# Robotics_Booster_Pack.net
KiCad netlist of a schematic drawn in EAGLE
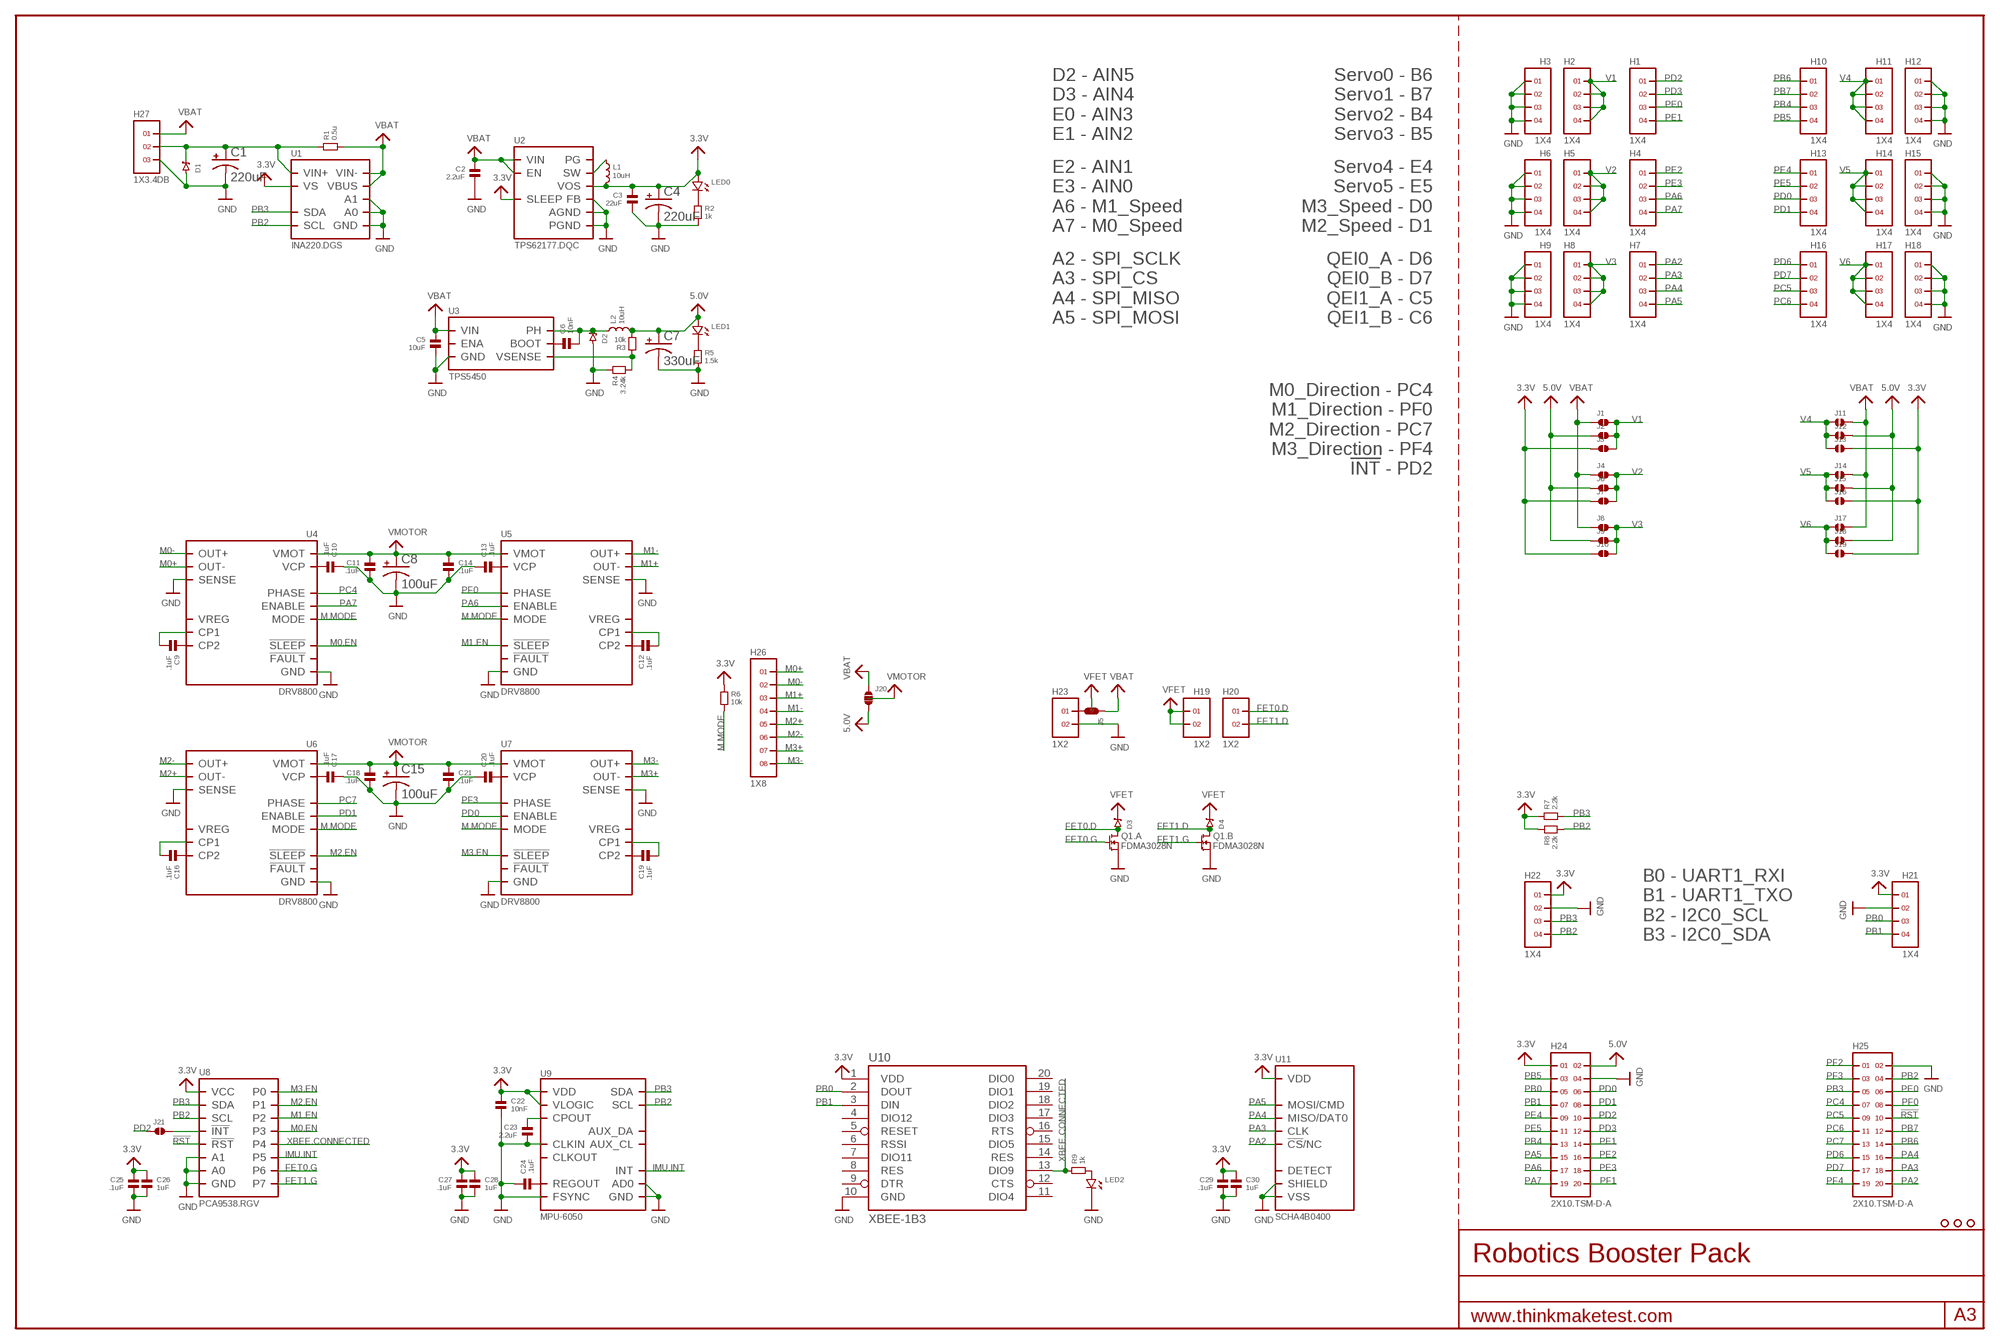
[diagram p0: schematic, sheet 1]

(export (version "E")
  (design (tool "Eeschema 10.0.6"))
  (components
    (comp (ref "C1")
      (value "220uF")
      (footprint "eagle-import:PANASONIC_E")
      (libsource (lib "eagle-import") (part "CPOL-USE"))
    )
    (comp (ref "C2")
      (value "2.2uF")
      (footprint "eagle-import:0603")
      (libsource (lib "eagle-import") (part "CAPACITOR.0603"))
    )
    (comp (ref "C3")
      (value "22uF")
      (footprint "eagle-import:0805")
      (libsource (lib "eagle-import") (part "CAPACITOR.0805"))
    )
    (comp (ref "C4")
      (value "220uF")
      (footprint "eagle-import:PANASONIC_E")
      (libsource (lib "eagle-import") (part "CPOL-USE"))
    )
    (comp (ref "C5")
      (value "10uF")
      (footprint "eagle-import:1206")
      (libsource (lib "eagle-import") (part "CAPACITOR.1206"))
    )
    (comp (ref "C6")
      (value "10nF")
      (footprint "eagle-import:0603")
      (libsource (lib "eagle-import") (part "CAPACITOR.0603"))
    )
    (comp (ref "C7")
      (value "330uF")
      (footprint "eagle-import:PANASONIC_E")
      (libsource (lib "eagle-import") (part "CPOL-USE"))
    )
    (comp (ref "C8")
      (value "100uF")
      (footprint "eagle-import:PANASONIC_E")
      (libsource (lib "eagle-import") (part "CPOL-USE"))
    )
    (comp (ref "C9")
      (value ".1uF")
      (footprint "eagle-import:0603")
      (libsource (lib "eagle-import") (part "CAPACITOR.0603"))
    )
    (comp (ref "C10")
      (value ".1uF")
      (footprint "eagle-import:0603")
      (libsource (lib "eagle-import") (part "CAPACITOR.0603"))
    )
    (comp (ref "C11")
      (value ".1uF")
      (footprint "eagle-import:0603")
      (libsource (lib "eagle-import") (part "CAPACITOR.0603"))
    )
    (comp (ref "C12")
      (value ".1uF")
      (footprint "eagle-import:0603")
      (libsource (lib "eagle-import") (part "CAPACITOR.0603"))
    )
    (comp (ref "C13")
      (value ".1uF")
      (footprint "eagle-import:0603")
      (libsource (lib "eagle-import") (part "CAPACITOR.0603"))
    )
    (comp (ref "C14")
      (value ".1uF")
      (footprint "eagle-import:0603")
      (libsource (lib "eagle-import") (part "CAPACITOR.0603"))
    )
    (comp (ref "C15")
      (value "100uF")
      (footprint "eagle-import:PANASONIC_E")
      (libsource (lib "eagle-import") (part "CPOL-USE"))
    )
    (comp (ref "C16")
      (value ".1uF")
      (footprint "eagle-import:0603")
      (libsource (lib "eagle-import") (part "CAPACITOR.0603"))
    )
    (comp (ref "C17")
      (value ".1uF")
      (footprint "eagle-import:0603")
      (libsource (lib "eagle-import") (part "CAPACITOR.0603"))
    )
    (comp (ref "C18")
      (value ".1uF")
      (footprint "eagle-import:0603")
      (libsource (lib "eagle-import") (part "CAPACITOR.0603"))
    )
    (comp (ref "C19")
      (value ".1uF")
      (footprint "eagle-import:0603")
      (libsource (lib "eagle-import") (part "CAPACITOR.0603"))
    )
    (comp (ref "C20")
      (value ".1uF")
      (footprint "eagle-import:0603")
      (libsource (lib "eagle-import") (part "CAPACITOR.0603"))
    )
    (comp (ref "C21")
      (value ".1uF")
      (footprint "eagle-import:0603")
      (libsource (lib "eagle-import") (part "CAPACITOR.0603"))
    )
    (comp (ref "C22")
      (value "10nF")
      (footprint "eagle-import:0603")
      (libsource (lib "eagle-import") (part "CAPACITOR.0603"))
    )
    (comp (ref "C23")
      (value "2.2uF")
      (footprint "eagle-import:0603")
      (libsource (lib "eagle-import") (part "CAPACITOR.0603"))
    )
    (comp (ref "C24")
      (value ".1uF")
      (footprint "eagle-import:0603")
      (libsource (lib "eagle-import") (part "CAPACITOR.0603"))
    )
    (comp (ref "C25")
      (value ".1uF")
      (footprint "eagle-import:0603")
      (libsource (lib "eagle-import") (part "CAPACITOR.0603"))
    )
    (comp (ref "C26")
      (value "1uF")
      (footprint "eagle-import:0603")
      (libsource (lib "eagle-import") (part "CAPACITOR.0603"))
    )
    (comp (ref "C27")
      (value ".1uF")
      (footprint "eagle-import:0603")
      (libsource (lib "eagle-import") (part "CAPACITOR.0603"))
    )
    (comp (ref "C28")
      (value "1uF")
      (footprint "eagle-import:0603")
      (libsource (lib "eagle-import") (part "CAPACITOR.0603"))
    )
    (comp (ref "C29")
      (value ".1uF")
      (footprint "eagle-import:0603")
      (libsource (lib "eagle-import") (part "CAPACITOR.0603"))
    )
    (comp (ref "C30")
      (value "1uF")
      (footprint "eagle-import:0603")
      (libsource (lib "eagle-import") (part "CAPACITOR.0603"))
    )
    (comp (ref "D1")
      (value "CDBMT2100-HF")
      (footprint "eagle-import:SOD-123H")
      (libsource (lib "eagle-import") (part "CDBMT____-HF"))
    )
    (comp (ref "D2")
      (value "CDBC5XXX-G")
      (footprint "eagle-import:DO-214AB")
      (libsource (lib "eagle-import") (part "CDBC5XXX-G"))
    )
    (comp (ref "D3")
      (value "CDBMT2100-HF")
      (footprint "eagle-import:SOD-123H")
      (libsource (lib "eagle-import") (part "CDBMT____-HF"))
    )
    (comp (ref "D4")
      (value "CDBMT2100-HF")
      (footprint "eagle-import:SOD-123H")
      (libsource (lib "eagle-import") (part "CDBMT____-HF"))
    )
    (comp (ref "H1")
      (value "1X4")
      (footprint "eagle-import:1X4")
      (libsource (lib "eagle-import") (part "1X4"))
    )
    (comp (ref "H2")
      (value "1X4")
      (footprint "eagle-import:1X4")
      (libsource (lib "eagle-import") (part "1X4"))
    )
    (comp (ref "H3")
      (value "1X4")
      (footprint "eagle-import:1X4")
      (libsource (lib "eagle-import") (part "1X4"))
    )
    (comp (ref "H4")
      (value "1X4")
      (footprint "eagle-import:1X4")
      (libsource (lib "eagle-import") (part "1X4"))
    )
    (comp (ref "H5")
      (value "1X4")
      (footprint "eagle-import:1X4")
      (libsource (lib "eagle-import") (part "1X4"))
    )
    (comp (ref "H6")
      (value "1X4")
      (footprint "eagle-import:1X4")
      (libsource (lib "eagle-import") (part "1X4"))
    )
    (comp (ref "H7")
      (value "1X4")
      (footprint "eagle-import:1X4")
      (libsource (lib "eagle-import") (part "1X4"))
    )
    (comp (ref "H8")
      (value "1X4")
      (footprint "eagle-import:1X4")
      (libsource (lib "eagle-import") (part "1X4"))
    )
    (comp (ref "H9")
      (value "1X4")
      (footprint "eagle-import:1X4")
      (libsource (lib "eagle-import") (part "1X4"))
    )
    (comp (ref "H10")
      (value "1X4")
      (footprint "eagle-import:1X4")
      (libsource (lib "eagle-import") (part "1X4"))
    )
    (comp (ref "H11")
      (value "1X4")
      (footprint "eagle-import:1X4")
      (libsource (lib "eagle-import") (part "1X4"))
    )
    (comp (ref "H12")
      (value "1X4")
      (footprint "eagle-import:1X4")
      (libsource (lib "eagle-import") (part "1X4"))
    )
    (comp (ref "H13")
      (value "1X4")
      (footprint "eagle-import:1X4")
      (libsource (lib "eagle-import") (part "1X4"))
    )
    (comp (ref "H14")
      (value "1X4")
      (footprint "eagle-import:1X4")
      (libsource (lib "eagle-import") (part "1X4"))
    )
    (comp (ref "H15")
      (value "1X4")
      (footprint "eagle-import:1X4")
      (libsource (lib "eagle-import") (part "1X4"))
    )
    (comp (ref "H16")
      (value "1X4")
      (footprint "eagle-import:1X4")
      (libsource (lib "eagle-import") (part "1X4"))
    )
    (comp (ref "H17")
      (value "1X4")
      (footprint "eagle-import:1X4")
      (libsource (lib "eagle-import") (part "1X4"))
    )
    (comp (ref "H18")
      (value "1X4")
      (footprint "eagle-import:1X4")
      (libsource (lib "eagle-import") (part "1X4"))
    )
    (comp (ref "H19")
      (value "1X2")
      (footprint "eagle-import:1X2")
      (libsource (lib "eagle-import") (part "1X2"))
    )
    (comp (ref "H20")
      (value "1X2")
      (footprint "eagle-import:1X2")
      (libsource (lib "eagle-import") (part "1X2"))
    )
    (comp (ref "H21")
      (value "1X4")
      (footprint "eagle-import:1X4")
      (libsource (lib "eagle-import") (part "1X4"))
    )
    (comp (ref "H22")
      (value "1X4")
      (footprint "eagle-import:1X4")
      (libsource (lib "eagle-import") (part "1X4"))
    )
    (comp (ref "H23")
      (value "1X2")
      (footprint "eagle-import:1X2")
      (libsource (lib "eagle-import") (part "1X2"))
    )
    (comp (ref "H24")
      (value "2X10.TSM-D-A")
      (footprint "eagle-import:TSM-110-XX-XXX-DV-A")
      (libsource (lib "eagle-import") (part "2X10.TSM-D-A"))
    )
    (comp (ref "H25")
      (value "2X10.TSM-D-A")
      (footprint "eagle-import:TSM-110-XX-XXX-DV-A")
      (libsource (lib "eagle-import") (part "2X10.TSM-D-A"))
    )
    (comp (ref "H26")
      (value "1X8")
      (footprint "eagle-import:1824480000")
      (libsource (lib "eagle-import") (part "1X8"))
    )
    (comp (ref "H27")
      (value "1X3.4DB")
      (footprint "eagle-import:4DB-P108-02")
      (libsource (lib "eagle-import") (part "1X3.4DB"))
    )
    (comp (ref "J1")
      (value "SOLDERJUMPER.2.LRG")
      (footprint "eagle-import:2.LRG")
      (libsource (lib "eagle-import") (part "SOLDERJUMPER.2.LRG"))
    )
    (comp (ref "J2")
      (value "SOLDERJUMPER.2.LRG")
      (footprint "eagle-import:2.LRG")
      (libsource (lib "eagle-import") (part "SOLDERJUMPER.2.LRG"))
    )
    (comp (ref "J3")
      (value "SOLDERJUMPER.2.LRG.PASTE")
      (footprint "eagle-import:2.LRG.PASTE")
      (libsource (lib "eagle-import") (part "SOLDERJUMPER.2.LRG.PASTE"))
    )
    (comp (ref "J4")
      (value "SOLDERJUMPER.2.LRG")
      (footprint "eagle-import:2.LRG")
      (libsource (lib "eagle-import") (part "SOLDERJUMPER.2.LRG"))
    )
    (comp (ref "J5")
      (value "SOLDERJUMPER.3.LRG.12")
      (footprint "eagle-import:3.LRG.12")
      (libsource (lib "eagle-import") (part "SOLDERJUMPER.3.LRG.12"))
    )
    (comp (ref "J6")
      (value "SOLDERJUMPER.2.LRG")
      (footprint "eagle-import:2.LRG")
      (libsource (lib "eagle-import") (part "SOLDERJUMPER.2.LRG"))
    )
    (comp (ref "J7")
      (value "SOLDERJUMPER.2.LRG.PASTE")
      (footprint "eagle-import:2.LRG.PASTE")
      (libsource (lib "eagle-import") (part "SOLDERJUMPER.2.LRG.PASTE"))
    )
    (comp (ref "J8")
      (value "SOLDERJUMPER.2.LRG")
      (footprint "eagle-import:2.LRG")
      (libsource (lib "eagle-import") (part "SOLDERJUMPER.2.LRG"))
    )
    (comp (ref "J9")
      (value "SOLDERJUMPER.2.LRG")
      (footprint "eagle-import:2.LRG")
      (libsource (lib "eagle-import") (part "SOLDERJUMPER.2.LRG"))
    )
    (comp (ref "J10")
      (value "SOLDERJUMPER.2.LRG.PASTE")
      (footprint "eagle-import:2.LRG.PASTE")
      (libsource (lib "eagle-import") (part "SOLDERJUMPER.2.LRG.PASTE"))
    )
    (comp (ref "J11")
      (value "SOLDERJUMPER.2.LRG")
      (footprint "eagle-import:2.LRG")
      (libsource (lib "eagle-import") (part "SOLDERJUMPER.2.LRG"))
    )
    (comp (ref "J12")
      (value "SOLDERJUMPER.2.LRG.PASTE")
      (footprint "eagle-import:2.LRG.PASTE")
      (libsource (lib "eagle-import") (part "SOLDERJUMPER.2.LRG.PASTE"))
    )
    (comp (ref "J13")
      (value "SOLDERJUMPER.2.LRG")
      (footprint "eagle-import:2.LRG")
      (libsource (lib "eagle-import") (part "SOLDERJUMPER.2.LRG"))
    )
    (comp (ref "J14")
      (value "SOLDERJUMPER.2.LRG")
      (footprint "eagle-import:2.LRG")
      (libsource (lib "eagle-import") (part "SOLDERJUMPER.2.LRG"))
    )
    (comp (ref "J15")
      (value "SOLDERJUMPER.2.LRG")
      (footprint "eagle-import:2.LRG")
      (libsource (lib "eagle-import") (part "SOLDERJUMPER.2.LRG"))
    )
    (comp (ref "J16")
      (value "SOLDERJUMPER.2.LRG.PASTE")
      (footprint "eagle-import:2.LRG.PASTE")
      (libsource (lib "eagle-import") (part "SOLDERJUMPER.2.LRG.PASTE"))
    )
    (comp (ref "J17")
      (value "SOLDERJUMPER.2.LRG")
      (footprint "eagle-import:2.LRG")
      (libsource (lib "eagle-import") (part "SOLDERJUMPER.2.LRG"))
    )
    (comp (ref "J18")
      (value "SOLDERJUMPER.2.LRG")
      (footprint "eagle-import:2.LRG")
      (libsource (lib "eagle-import") (part "SOLDERJUMPER.2.LRG"))
    )
    (comp (ref "J19")
      (value "SOLDERJUMPER.2.LRG.PASTE")
      (footprint "eagle-import:2.LRG.PASTE")
      (libsource (lib "eagle-import") (part "SOLDERJUMPER.2.LRG.PASTE"))
    )
    (comp (ref "J20")
      (value "SOLDERJUMPER.3.LRG.12")
      (footprint "eagle-import:3.LRG.12")
      (libsource (lib "eagle-import") (part "SOLDERJUMPER.3.LRG.12"))
    )
    (comp (ref "J21")
      (value "SOLDERJUMPER.2.LRG")
      (footprint "eagle-import:2.LRG")
      (libsource (lib "eagle-import") (part "SOLDERJUMPER.2.LRG"))
    )
    (comp (ref "L1")
      (value "10uH")
      (footprint "eagle-import:SRN6045")
      (libsource (lib "eagle-import") (part "INDUCTOR-SRN6045"))
    )
    (comp (ref "L2")
      (value "10uH")
      (footprint "eagle-import:XAL6060")
      (libsource (lib "eagle-import") (part "INDUCTOR.XAL6060"))
    )
    (comp (ref "LED0")
      (value "LED.0603")
      (footprint "eagle-import:0603.LED")
      (libsource (lib "eagle-import") (part "LED.0603"))
    )
    (comp (ref "LED1")
      (value "LED.0603")
      (footprint "eagle-import:0603.LED")
      (libsource (lib "eagle-import") (part "LED.0603"))
    )
    (comp (ref "LED2")
      (value "LED.0603")
      (footprint "eagle-import:0603.LED")
      (libsource (lib "eagle-import") (part "LED.0603"))
    )
    (comp (ref "Q1")
      (value "FDMA3028N")
      (footprint "eagle-import:MICROFET.2X2")
      (libsource (lib "eagle-import") (part "FDMA"))
    )
    (comp (ref "R1")
      (value "0.5u")
      (footprint "eagle-import:2512")
      (libsource (lib "eagle-import") (part "RESISTOR.2512"))
    )
    (comp (ref "R2")
      (value "1k")
      (footprint "eagle-import:0603")
      (libsource (lib "eagle-import") (part "RESISTOR.0603"))
    )
    (comp (ref "R3")
      (value "10k")
      (footprint "eagle-import:0603")
      (libsource (lib "eagle-import") (part "RESISTOR.0603"))
    )
    (comp (ref "R4")
      (value "3.24k")
      (footprint "eagle-import:0603")
      (libsource (lib "eagle-import") (part "RESISTOR.0603"))
    )
    (comp (ref "R5")
      (value "1.5k")
      (footprint "eagle-import:0603")
      (libsource (lib "eagle-import") (part "RESISTOR.0603"))
    )
    (comp (ref "R6")
      (value "10k")
      (footprint "eagle-import:0603")
      (libsource (lib "eagle-import") (part "RESISTOR.0603"))
    )
    (comp (ref "R7")
      (value "2.2k")
      (footprint "eagle-import:0603")
      (libsource (lib "eagle-import") (part "RESISTOR.0603"))
    )
    (comp (ref "R8")
      (value "2.2k")
      (footprint "eagle-import:0603")
      (libsource (lib "eagle-import") (part "RESISTOR.0603"))
    )
    (comp (ref "R9")
      (value "1k")
      (footprint "eagle-import:0603")
      (libsource (lib "eagle-import") (part "RESISTOR.0603"))
    )
    (comp (ref "U$3")
      (value "HOLE.4MM")
      (footprint "eagle-import:#4")
      (libsource (lib "eagle-import") (part "HOLE.4MM"))
    )
    (comp (ref "U$4")
      (value "HOLE.4MM")
      (footprint "eagle-import:#4")
      (libsource (lib "eagle-import") (part "HOLE.4MM"))
    )
    (comp (ref "U$21")
      (value "HOLE.4MM")
      (footprint "eagle-import:#4")
      (libsource (lib "eagle-import") (part "HOLE.4MM"))
    )
    (comp (ref "U1")
      (value "INA220.DGS")
      (footprint "eagle-import:DGS.10")
      (libsource (lib "eagle-import") (part "INA220.DGS"))
    )
    (comp (ref "U2")
      (value "TPS62177.DQC")
      (footprint "eagle-import:DQC")
      (libsource (lib "eagle-import") (part "TPS62177.DQC"))
    )
    (comp (ref "U3")
      (value "TPS5450")
      (footprint "eagle-import:DDA")
      (libsource (lib "eagle-import") (part "TPS54X0"))
    )
    (comp (ref "U4")
      (value "DRV8800")
      (footprint "eagle-import:RTY.16")
      (libsource (lib "eagle-import") (part "DRV8800.RTY"))
    )
    (comp (ref "U5")
      (value "DRV8800")
      (footprint "eagle-import:RTY.16")
      (libsource (lib "eagle-import") (part "DRV8800.RTY"))
    )
    (comp (ref "U6")
      (value "DRV8800")
      (footprint "eagle-import:RTY.16")
      (libsource (lib "eagle-import") (part "DRV8800.RTY"))
    )
    (comp (ref "U7")
      (value "DRV8800")
      (footprint "eagle-import:RTY.16")
      (libsource (lib "eagle-import") (part "DRV8800.RTY"))
    )
    (comp (ref "U8")
      (value "PCA9538.RGV")
      (footprint "eagle-import:RGV.16")
      (libsource (lib "eagle-import") (part "PCA9538.RGV"))
    )
    (comp (ref "U9")
      (value "MPU-6050")
      (footprint "eagle-import:QFN.24.4X4")
      (libsource (lib "eagle-import") (part "MPU-6050"))
    )
    (comp (ref "U10")
      (value "XBEE-1B3")
      (footprint "eagle-import:XBEE-SMD")
      (libsource (lib "eagle-import") (part "XBEE-1B3"))
    )
    (comp (ref "U11")
      (value "SCHA4B0400")
      (footprint "eagle-import:SCHA4B0400")
      (libsource (lib "eagle-import") (part "SCHA4B0400"))
    )
  )
  (nets
    (net (code "1") (name "/FET0.D") (class "Default")
      (node (ref "D3") (pin "2") (pinfunction "2_2") (pintype "bidirectional"))
      (node (ref "H20") (pin "1") (pinfunction "1_1") (pintype "bidirectional"))
      (node (ref "Q1") (pin "6") (pinfunction "D_6") (pintype "bidirectional"))
      (node (ref "Q1") (pin "PAD@1") (pinfunction "D_PAD@1") (pintype "bidirectional"))
    )
    (net (code "2") (name "/FET0.G") (class "Default")
      (node (ref "Q1") (pin "2") (pinfunction "G_2") (pintype "bidirectional"))
      (node (ref "U8") (pin "9") (pinfunction "P6_9") (pintype "bidirectional"))
    )
    (net (code "3") (name "/FET1.D") (class "Default")
      (node (ref "D4") (pin "2") (pinfunction "2_2") (pintype "bidirectional"))
      (node (ref "H20") (pin "2") (pinfunction "2_2") (pintype "bidirectional"))
      (node (ref "Q1") (pin "3") (pinfunction "D_3") (pintype "bidirectional"))
      (node (ref "Q1") (pin "PAD@2") (pinfunction "D_PAD@2") (pintype "bidirectional"))
    )
    (net (code "4") (name "/FET1.G") (class "Default")
      (node (ref "Q1") (pin "5") (pinfunction "G_5") (pintype "bidirectional"))
      (node (ref "U8") (pin "10") (pinfunction "P7_10") (pintype "bidirectional"))
    )
    (net (code "5") (name "/IMU.INT") (class "Default")
      (node (ref "U8") (pin "8") (pinfunction "P5_8") (pintype "bidirectional"))
      (node (ref "U9") (pin "12") (pinfunction "INT_12") (pintype "bidirectional"))
    )
    (net (code "6") (name "/M.MODE") (class "Default")
      (node (ref "R6") (pin "2") (pinfunction "2_2") (pintype "bidirectional"))
      (node (ref "U4") (pin "16") (pinfunction "MODE_16") (pintype "bidirectional"))
      (node (ref "U5") (pin "16") (pinfunction "MODE_16") (pintype "bidirectional"))
      (node (ref "U6") (pin "16") (pinfunction "MODE_16") (pintype "bidirectional"))
      (node (ref "U7") (pin "16") (pinfunction "MODE_16") (pintype "bidirectional"))
    )
    (net (code "7") (name "/M0+") (class "Default")
      (node (ref "H26") (pin "1@1") (pinfunction "1_1@1") (pintype "bidirectional"))
      (node (ref "H26") (pin "1@2") (pinfunction "1_1@2") (pintype "bidirectional"))
      (node (ref "U4") (pin "9") (pinfunction "OUT-_9") (pintype "bidirectional"))
    )
    (net (code "8") (name "/M0-") (class "Default")
      (node (ref "H26") (pin "2@1") (pinfunction "2_2@1") (pintype "bidirectional"))
      (node (ref "H26") (pin "2@2") (pinfunction "2_2@2") (pintype "bidirectional"))
      (node (ref "U4") (pin "6") (pinfunction "OUT+_6") (pintype "bidirectional"))
    )
    (net (code "9") (name "/M0.EN") (class "Default")
      (node (ref "U4") (pin "3") (pinfunction "~{SLEEP}_3") (pintype "bidirectional"))
      (node (ref "U8") (pin "5") (pinfunction "P3_5") (pintype "bidirectional"))
    )
    (net (code "10") (name "/M1+") (class "Default")
      (node (ref "H26") (pin "3@1") (pinfunction "3_3@1") (pintype "bidirectional"))
      (node (ref "H26") (pin "3@2") (pinfunction "3_3@2") (pintype "bidirectional"))
      (node (ref "U5") (pin "9") (pinfunction "OUT-_9") (pintype "bidirectional"))
    )
    (net (code "11") (name "/M1-") (class "Default")
      (node (ref "H26") (pin "4@1") (pinfunction "4_4@1") (pintype "bidirectional"))
      (node (ref "H26") (pin "4@2") (pinfunction "4_4@2") (pintype "bidirectional"))
      (node (ref "U5") (pin "6") (pinfunction "OUT+_6") (pintype "bidirectional"))
    )
    (net (code "12") (name "/M1.EN") (class "Default")
      (node (ref "U5") (pin "3") (pinfunction "~{SLEEP}_3") (pintype "bidirectional"))
      (node (ref "U8") (pin "4") (pinfunction "P2_4") (pintype "bidirectional"))
    )
    (net (code "13") (name "/M2+") (class "Default")
      (node (ref "H26") (pin "5@1") (pinfunction "5_5@1") (pintype "bidirectional"))
      (node (ref "H26") (pin "5@2") (pinfunction "5_5@2") (pintype "bidirectional"))
      (node (ref "U6") (pin "9") (pinfunction "OUT-_9") (pintype "bidirectional"))
    )
    (net (code "14") (name "/M2-") (class "Default")
      (node (ref "H26") (pin "6@1") (pinfunction "6_6@1") (pintype "bidirectional"))
      (node (ref "H26") (pin "6@2") (pinfunction "6_6@2") (pintype "bidirectional"))
      (node (ref "U6") (pin "6") (pinfunction "OUT+_6") (pintype "bidirectional"))
    )
    (net (code "15") (name "/M2.EN") (class "Default")
      (node (ref "U6") (pin "3") (pinfunction "~{SLEEP}_3") (pintype "bidirectional"))
      (node (ref "U8") (pin "3") (pinfunction "P1_3") (pintype "bidirectional"))
    )
    (net (code "16") (name "/M3+") (class "Default")
      (node (ref "H26") (pin "7@1") (pinfunction "7_7@1") (pintype "bidirectional"))
      (node (ref "H26") (pin "7@2") (pinfunction "7_7@2") (pintype "bidirectional"))
      (node (ref "U7") (pin "9") (pinfunction "OUT-_9") (pintype "bidirectional"))
    )
    (net (code "17") (name "/M3-") (class "Default")
      (node (ref "H26") (pin "8@1") (pinfunction "8_8@1") (pintype "bidirectional"))
      (node (ref "H26") (pin "8@2") (pinfunction "8_8@2") (pintype "bidirectional"))
      (node (ref "U7") (pin "6") (pinfunction "OUT+_6") (pintype "bidirectional"))
    )
    (net (code "18") (name "/M3.EN") (class "Default")
      (node (ref "U7") (pin "3") (pinfunction "~{SLEEP}_3") (pintype "bidirectional"))
      (node (ref "U8") (pin "2") (pinfunction "P0_2") (pintype "bidirectional"))
    )
    (net (code "19") (name "/PA2") (class "Default")
      (node (ref "H25") (pin "20") (pinfunction "20_20") (pintype "bidirectional"))
      (node (ref "H7") (pin "1") (pinfunction "1_1") (pintype "bidirectional"))
      (node (ref "U11") (pin "!CS!/NC/DAT3") (pinfunction "~{CS}/NC_!CS!/NC/DAT3") (pintype "bidirectional"))
    )
    (net (code "20") (name "/PA3") (class "Default")
      (node (ref "H25") (pin "18") (pinfunction "18_18") (pintype "bidirectional"))
      (node (ref "H7") (pin "2") (pinfunction "2_2") (pintype "bidirectional"))
      (node (ref "U11") (pin "CLK") (pinfunction "CLK_CLK") (pintype "bidirectional"))
    )
    (net (code "21") (name "/PA4") (class "Default")
      (node (ref "H25") (pin "16") (pinfunction "16_16") (pintype "bidirectional"))
      (node (ref "H7") (pin "3") (pinfunction "3_3") (pintype "bidirectional"))
      (node (ref "U11") (pin "MISO/DAT0") (pinfunction "MISO/DAT0_MISO/DAT0") (pintype "bidirectional"))
    )
    (net (code "22") (name "/PA5") (class "Default")
      (node (ref "H24") (pin "15") (pinfunction "15_15") (pintype "bidirectional"))
      (node (ref "H7") (pin "4") (pinfunction "4_4") (pintype "bidirectional"))
      (node (ref "U11") (pin "MOSI/CMD") (pinfunction "MOSI/CMD_MOSI/CMD") (pintype "bidirectional"))
    )
    (net (code "23") (name "/PA6") (class "Default")
      (node (ref "H24") (pin "17") (pinfunction "17_17") (pintype "bidirectional"))
      (node (ref "H4") (pin "3") (pinfunction "3_3") (pintype "bidirectional"))
      (node (ref "U5") (pin "4") (pinfunction "ENABLE_4") (pintype "bidirectional"))
    )
    (net (code "24") (name "/PA7") (class "Default")
      (node (ref "H24") (pin "19") (pinfunction "19_19") (pintype "bidirectional"))
      (node (ref "H4") (pin "4") (pinfunction "4_4") (pintype "bidirectional"))
      (node (ref "U4") (pin "4") (pinfunction "ENABLE_4") (pintype "bidirectional"))
    )
    (net (code "25") (name "/PB0") (class "Default")
      (node (ref "H21") (pin "3") (pinfunction "3_3") (pintype "bidirectional"))
      (node (ref "H24") (pin "5") (pinfunction "5_5") (pintype "bidirectional"))
      (node (ref "U10") (pin "2") (pinfunction "DOUT_2") (pintype "output"))
    )
    (net (code "26") (name "/PB1") (class "Default")
      (node (ref "H21") (pin "4") (pinfunction "4_4") (pintype "bidirectional"))
      (node (ref "H24") (pin "7") (pinfunction "7_7") (pintype "bidirectional"))
      (node (ref "U10") (pin "3") (pinfunction "DIN_3") (pintype "input"))
    )
    (net (code "27") (name "/PB2") (class "Default")
      (node (ref "H22") (pin "4") (pinfunction "4_4") (pintype "bidirectional"))
      (node (ref "H25") (pin "4") (pinfunction "4_4") (pintype "bidirectional"))
      (node (ref "R8") (pin "2") (pinfunction "2_2") (pintype "bidirectional"))
      (node (ref "U1") (pin "5") (pinfunction "SCL_5") (pintype "bidirectional"))
      (node (ref "U8") (pin "12") (pinfunction "SCL_12") (pintype "bidirectional"))
      (node (ref "U9") (pin "23") (pinfunction "SCL_23") (pintype "bidirectional"))
    )
    (net (code "28") (name "/PB3") (class "Default")
      (node (ref "H22") (pin "3") (pinfunction "3_3") (pintype "bidirectional"))
      (node (ref "H25") (pin "5") (pinfunction "5_5") (pintype "bidirectional"))
      (node (ref "R7") (pin "2") (pinfunction "2_2") (pintype "bidirectional"))
      (node (ref "U1") (pin "4") (pinfunction "SDA_4") (pintype "bidirectional"))
      (node (ref "U8") (pin "13") (pinfunction "SDA_13") (pintype "bidirectional"))
      (node (ref "U9") (pin "24") (pinfunction "SDA_24") (pintype "bidirectional"))
    )
    (net (code "29") (name "/PB4") (class "Default")
      (node (ref "H10") (pin "3") (pinfunction "3_3") (pintype "bidirectional"))
      (node (ref "H24") (pin "13") (pinfunction "13_13") (pintype "bidirectional"))
    )
    (net (code "30") (name "/PB5") (class "Default")
      (node (ref "H10") (pin "4") (pinfunction "4_4") (pintype "bidirectional"))
      (node (ref "H24") (pin "3") (pinfunction "3_3") (pintype "bidirectional"))
    )
    (net (code "31") (name "/PB6") (class "Default")
      (node (ref "H10") (pin "1") (pinfunction "1_1") (pintype "bidirectional"))
      (node (ref "H25") (pin "14") (pinfunction "14_14") (pintype "bidirectional"))
    )
    (net (code "32") (name "/PB7") (class "Default")
      (node (ref "H10") (pin "2") (pinfunction "2_2") (pintype "bidirectional"))
      (node (ref "H25") (pin "12") (pinfunction "12_12") (pintype "bidirectional"))
    )
    (net (code "33") (name "/PC4") (class "Default")
      (node (ref "H25") (pin "7") (pinfunction "7_7") (pintype "bidirectional"))
      (node (ref "U4") (pin "1") (pinfunction "PHASE_1") (pintype "bidirectional"))
    )
    (net (code "34") (name "/PC5") (class "Default")
      (node (ref "H16") (pin "3") (pinfunction "3_3") (pintype "bidirectional"))
      (node (ref "H25") (pin "9") (pinfunction "9_9") (pintype "bidirectional"))
    )
    (net (code "35") (name "/PC6") (class "Default")
      (node (ref "H16") (pin "4") (pinfunction "4_4") (pintype "bidirectional"))
      (node (ref "H25") (pin "11") (pinfunction "11_11") (pintype "bidirectional"))
    )
    (net (code "36") (name "/PC7") (class "Default")
      (node (ref "H25") (pin "13") (pinfunction "13_13") (pintype "bidirectional"))
      (node (ref "U6") (pin "1") (pinfunction "PHASE_1") (pintype "bidirectional"))
    )
    (net (code "37") (name "/PD0") (class "Default")
      (node (ref "H13") (pin "3") (pinfunction "3_3") (pintype "bidirectional"))
      (node (ref "H24") (pin "6") (pinfunction "6_6") (pintype "bidirectional"))
      (node (ref "U7") (pin "4") (pinfunction "ENABLE_4") (pintype "bidirectional"))
    )
    (net (code "38") (name "/PD1") (class "Default")
      (node (ref "H13") (pin "4") (pinfunction "4_4") (pintype "bidirectional"))
      (node (ref "H24") (pin "8") (pinfunction "8_8") (pintype "bidirectional"))
      (node (ref "U6") (pin "4") (pinfunction "ENABLE_4") (pintype "bidirectional"))
    )
    (net (code "39") (name "/PD2") (class "Default")
      (node (ref "H1") (pin "1") (pinfunction "1_1") (pintype "bidirectional"))
      (node (ref "H24") (pin "10") (pinfunction "10_10") (pintype "bidirectional"))
      (node (ref "J21") (pin "1") (pinfunction "1_1") (pintype "bidirectional"))
    )
    (net (code "40") (name "/PD3") (class "Default")
      (node (ref "H1") (pin "2") (pinfunction "2_2") (pintype "bidirectional"))
      (node (ref "H24") (pin "12") (pinfunction "12_12") (pintype "bidirectional"))
    )
    (net (code "41") (name "/PD6") (class "Default")
      (node (ref "H16") (pin "1") (pinfunction "1_1") (pintype "bidirectional"))
      (node (ref "H25") (pin "15") (pinfunction "15_15") (pintype "bidirectional"))
    )
    (net (code "42") (name "/PD7") (class "Default")
      (node (ref "H16") (pin "2") (pinfunction "2_2") (pintype "bidirectional"))
      (node (ref "H25") (pin "17") (pinfunction "17_17") (pintype "bidirectional"))
    )
    (net (code "43") (name "/PE0") (class "Default")
      (node (ref "H1") (pin "3") (pinfunction "3_3") (pintype "bidirectional"))
      (node (ref "H25") (pin "6") (pinfunction "6_6") (pintype "bidirectional"))
    )
    (net (code "44") (name "/PE1") (class "Default")
      (node (ref "H1") (pin "4") (pinfunction "4_4") (pintype "bidirectional"))
      (node (ref "H24") (pin "14") (pinfunction "14_14") (pintype "bidirectional"))
    )
    (net (code "45") (name "/PE2") (class "Default")
      (node (ref "H24") (pin "16") (pinfunction "16_16") (pintype "bidirectional"))
      (node (ref "H4") (pin "1") (pinfunction "1_1") (pintype "bidirectional"))
    )
    (net (code "46") (name "/PE3") (class "Default")
      (node (ref "H24") (pin "18") (pinfunction "18_18") (pintype "bidirectional"))
      (node (ref "H4") (pin "2") (pinfunction "2_2") (pintype "bidirectional"))
    )
    (net (code "47") (name "/PE4") (class "Default")
      (node (ref "H13") (pin "1") (pinfunction "1_1") (pintype "bidirectional"))
      (node (ref "H24") (pin "9") (pinfunction "9_9") (pintype "bidirectional"))
    )
    (net (code "48") (name "/PE5") (class "Default")
      (node (ref "H13") (pin "2") (pinfunction "2_2") (pintype "bidirectional"))
      (node (ref "H24") (pin "11") (pinfunction "11_11") (pintype "bidirectional"))
    )
    (net (code "49") (name "/PF0") (class "Default")
      (node (ref "H25") (pin "8") (pinfunction "8_8") (pintype "bidirectional"))
      (node (ref "U5") (pin "1") (pinfunction "PHASE_1") (pintype "bidirectional"))
    )
    (net (code "50") (name "/PF1") (class "Default")
      (node (ref "H24") (pin "20") (pinfunction "20_20") (pintype "bidirectional"))
    )
    (net (code "51") (name "/PF2") (class "Default")
      (node (ref "H25") (pin "1") (pinfunction "1_1") (pintype "bidirectional"))
    )
    (net (code "52") (name "/PF3") (class "Default")
      (node (ref "H25") (pin "3") (pinfunction "3_3") (pintype "bidirectional"))
      (node (ref "U7") (pin "1") (pinfunction "PHASE_1") (pintype "bidirectional"))
    )
    (net (code "53") (name "/PF4") (class "Default")
      (node (ref "H25") (pin "19") (pinfunction "19_19") (pintype "bidirectional"))
    )
    (net (code "54") (name "/V1") (class "Default")
      (node (ref "H2") (pin "1") (pinfunction "1_1") (pintype "bidirectional"))
      (node (ref "H2") (pin "2") (pinfunction "2_2") (pintype "bidirectional"))
      (node (ref "H2") (pin "3") (pinfunction "3_3") (pintype "bidirectional"))
      (node (ref "H2") (pin "4") (pinfunction "4_4") (pintype "bidirectional"))
      (node (ref "J1") (pin "2") (pinfunction "2_2") (pintype "bidirectional"))
      (node (ref "J2") (pin "2") (pinfunction "2_2") (pintype "bidirectional"))
      (node (ref "J3") (pin "2") (pinfunction "2_2") (pintype "bidirectional"))
    )
    (net (code "55") (name "/V2") (class "Default")
      (node (ref "H5") (pin "1") (pinfunction "1_1") (pintype "bidirectional"))
      (node (ref "H5") (pin "2") (pinfunction "2_2") (pintype "bidirectional"))
      (node (ref "H5") (pin "3") (pinfunction "3_3") (pintype "bidirectional"))
      (node (ref "H5") (pin "4") (pinfunction "4_4") (pintype "bidirectional"))
      (node (ref "J4") (pin "2") (pinfunction "2_2") (pintype "bidirectional"))
      (node (ref "J6") (pin "2") (pinfunction "2_2") (pintype "bidirectional"))
      (node (ref "J7") (pin "2") (pinfunction "2_2") (pintype "bidirectional"))
    )
    (net (code "56") (name "/V3") (class "Default")
      (node (ref "H8") (pin "1") (pinfunction "1_1") (pintype "bidirectional"))
      (node (ref "H8") (pin "2") (pinfunction "2_2") (pintype "bidirectional"))
      (node (ref "H8") (pin "3") (pinfunction "3_3") (pintype "bidirectional"))
      (node (ref "H8") (pin "4") (pinfunction "4_4") (pintype "bidirectional"))
      (node (ref "J10") (pin "2") (pinfunction "2_2") (pintype "bidirectional"))
      (node (ref "J8") (pin "2") (pinfunction "2_2") (pintype "bidirectional"))
      (node (ref "J9") (pin "2") (pinfunction "2_2") (pintype "bidirectional"))
    )
    (net (code "57") (name "/V4") (class "Default")
      (node (ref "H11") (pin "1") (pinfunction "1_1") (pintype "bidirectional"))
      (node (ref "H11") (pin "2") (pinfunction "2_2") (pintype "bidirectional"))
      (node (ref "H11") (pin "3") (pinfunction "3_3") (pintype "bidirectional"))
      (node (ref "H11") (pin "4") (pinfunction "4_4") (pintype "bidirectional"))
      (node (ref "J11") (pin "2") (pinfunction "2_2") (pintype "bidirectional"))
      (node (ref "J12") (pin "2") (pinfunction "2_2") (pintype "bidirectional"))
      (node (ref "J13") (pin "2") (pinfunction "2_2") (pintype "bidirectional"))
    )
    (net (code "58") (name "/V5") (class "Default")
      (node (ref "H14") (pin "1") (pinfunction "1_1") (pintype "bidirectional"))
      (node (ref "H14") (pin "2") (pinfunction "2_2") (pintype "bidirectional"))
      (node (ref "H14") (pin "3") (pinfunction "3_3") (pintype "bidirectional"))
      (node (ref "H14") (pin "4") (pinfunction "4_4") (pintype "bidirectional"))
      (node (ref "J14") (pin "2") (pinfunction "2_2") (pintype "bidirectional"))
      (node (ref "J15") (pin "2") (pinfunction "2_2") (pintype "bidirectional"))
      (node (ref "J16") (pin "2") (pinfunction "2_2") (pintype "bidirectional"))
    )
    (net (code "59") (name "/V6") (class "Default")
      (node (ref "H17") (pin "1") (pinfunction "1_1") (pintype "bidirectional"))
      (node (ref "H17") (pin "2") (pinfunction "2_2") (pintype "bidirectional"))
      (node (ref "H17") (pin "3") (pinfunction "3_3") (pintype "bidirectional"))
      (node (ref "H17") (pin "4") (pinfunction "4_4") (pintype "bidirectional"))
      (node (ref "J17") (pin "2") (pinfunction "2_2") (pintype "bidirectional"))
      (node (ref "J18") (pin "2") (pinfunction "2_2") (pintype "bidirectional"))
      (node (ref "J19") (pin "2") (pinfunction "2_2") (pintype "bidirectional"))
    )
    (net (code "60") (name "/XBEE.CONNECTED") (class "Default")
      (node (ref "R9") (pin "1") (pinfunction "1_1") (pintype "bidirectional"))
      (node (ref "U10") (pin "13") (pinfunction "DIO9_13") (pintype "bidirectional"))
      (node (ref "U8") (pin "7") (pinfunction "P4_7") (pintype "bidirectional"))
    )
    (net (code "61") (name "/~{RST}") (class "Default")
      (node (ref "H25") (pin "10") (pinfunction "10_10") (pintype "bidirectional"))
      (node (ref "U8") (pin "1") (pinfunction "~{RST}_1") (pintype "bidirectional"))
    )
    (net (code "62") (name "3.3V") (class "Default")
      (node (ref "C22") (pin "1") (pinfunction "1_1") (pintype "bidirectional"))
      (node (ref "C25") (pin "1") (pinfunction "1_1") (pintype "bidirectional"))
      (node (ref "C26") (pin "1") (pinfunction "1_1") (pintype "bidirectional"))
      (node (ref "C27") (pin "1") (pinfunction "1_1") (pintype "bidirectional"))
      (node (ref "C28") (pin "1") (pinfunction "1_1") (pintype "bidirectional"))
      (node (ref "C29") (pin "1") (pinfunction "1_1") (pintype "bidirectional"))
      (node (ref "C3") (pin "1") (pinfunction "1_1") (pintype "bidirectional"))
      (node (ref "C30") (pin "1") (pinfunction "1_1") (pintype "bidirectional"))
      (node (ref "C4") (pin "+") (pinfunction "+_+") (pintype "passive"))
      (node (ref "H21") (pin "1") (pinfunction "1_1") (pintype "bidirectional"))
      (node (ref "H22") (pin "1") (pinfunction "1_1") (pintype "bidirectional"))
      (node (ref "H24") (pin "1") (pinfunction "1_1") (pintype "bidirectional"))
      (node (ref "J10") (pin "1") (pinfunction "1_1") (pintype "bidirectional"))
      (node (ref "J13") (pin "1") (pinfunction "1_1") (pintype "bidirectional"))
      (node (ref "J16") (pin "1") (pinfunction "1_1") (pintype "bidirectional"))
      (node (ref "J19") (pin "1") (pinfunction "1_1") (pintype "bidirectional"))
      (node (ref "J3") (pin "1") (pinfunction "1_1") (pintype "bidirectional"))
      (node (ref "J7") (pin "1") (pinfunction "1_1") (pintype "bidirectional"))
      (node (ref "L1") (pin "2") (pinfunction "2_2") (pintype "passive"))
      (node (ref "LED0") (pin "P$1") (pinfunction "1_P$1") (pintype "bidirectional"))
      (node (ref "R6") (pin "1") (pinfunction "1_1") (pintype "bidirectional"))
      (node (ref "R7") (pin "1") (pinfunction "1_1") (pintype "bidirectional"))
      (node (ref "R8") (pin "1") (pinfunction "1_1") (pintype "bidirectional"))
      (node (ref "U1") (pin "6") (pinfunction "VS_6") (pintype "bidirectional"))
      (node (ref "U10") (pin "1") (pinfunction "VDD_1") (pintype "power_in"))
      (node (ref "U11") (pin "VDD") (pinfunction "VDD_VDD") (pintype "bidirectional"))
      (node (ref "U2") (pin "10") (pinfunction "VOS_10") (pintype "bidirectional"))
      (node (ref "U2") (pin "8") (pinfunction "SLEEP_8") (pintype "bidirectional"))
      (node (ref "U8") (pin "14") (pinfunction "VCC_14") (pintype "bidirectional"))
      (node (ref "U9") (pin "13") (pinfunction "VDD_13") (pintype "bidirectional"))
      (node (ref "U9") (pin "8") (pinfunction "VLOGIC_8") (pintype "bidirectional"))
    )
    (net (code "63") (name "5.0V") (class "Default")
      (node (ref "C7") (pin "+") (pinfunction "+_+") (pintype "passive"))
      (node (ref "H24") (pin "2") (pinfunction "2_2") (pintype "bidirectional"))
      (node (ref "J12") (pin "1") (pinfunction "1_1") (pintype "bidirectional"))
      (node (ref "J15") (pin "1") (pinfunction "1_1") (pintype "bidirectional"))
      (node (ref "J18") (pin "1") (pinfunction "1_1") (pintype "bidirectional"))
      (node (ref "J2") (pin "1") (pinfunction "1_1") (pintype "bidirectional"))
      (node (ref "J20") (pin "3") (pinfunction "3_3") (pintype "bidirectional"))
      (node (ref "J6") (pin "1") (pinfunction "1_1") (pintype "bidirectional"))
      (node (ref "J9") (pin "1") (pinfunction "1_1") (pintype "bidirectional"))
      (node (ref "L2") (pin "2") (pinfunction "2_2") (pintype "passive"))
      (node (ref "LED1") (pin "P$1") (pinfunction "1_P$1") (pintype "bidirectional"))
      (node (ref "R3") (pin "2") (pinfunction "2_2") (pintype "bidirectional"))
    )
    (net (code "64") (name "GND") (class "Default")
      (node (ref "C1") (pin "-") (pinfunction "-_-") (pintype "passive"))
      (node (ref "C10") (pin "1") (pinfunction "1_1") (pintype "bidirectional"))
      (node (ref "C11") (pin "2") (pinfunction "2_2") (pintype "bidirectional"))
      (node (ref "C13") (pin "1") (pinfunction "1_1") (pintype "bidirectional"))
      (node (ref "C14") (pin "2") (pinfunction "2_2") (pintype "bidirectional"))
      (node (ref "C15") (pin "-") (pinfunction "-_-") (pintype "passive"))
      (node (ref "C17") (pin "1") (pinfunction "1_1") (pintype "bidirectional"))
      (node (ref "C18") (pin "2") (pinfunction "2_2") (pintype "bidirectional"))
      (node (ref "C2") (pin "2") (pinfunction "2_2") (pintype "bidirectional"))
      (node (ref "C20") (pin "1") (pinfunction "1_1") (pintype "bidirectional"))
      (node (ref "C21") (pin "2") (pinfunction "2_2") (pintype "bidirectional"))
      (node (ref "C22") (pin "2") (pinfunction "2_2") (pintype "bidirectional"))
      (node (ref "C23") (pin "2") (pinfunction "2_2") (pintype "bidirectional"))
      (node (ref "C24") (pin "1") (pinfunction "1_1") (pintype "bidirectional"))
      (node (ref "C25") (pin "2") (pinfunction "2_2") (pintype "bidirectional"))
      (node (ref "C26") (pin "2") (pinfunction "2_2") (pintype "bidirectional"))
      (node (ref "C27") (pin "2") (pinfunction "2_2") (pintype "bidirectional"))
      (node (ref "C28") (pin "2") (pinfunction "2_2") (pintype "bidirectional"))
      (node (ref "C29") (pin "2") (pinfunction "2_2") (pintype "bidirectional"))
      (node (ref "C3") (pin "2") (pinfunction "2_2") (pintype "bidirectional"))
      (node (ref "C30") (pin "2") (pinfunction "2_2") (pintype "bidirectional"))
      (node (ref "C4") (pin "-") (pinfunction "-_-") (pintype "passive"))
      (node (ref "C5") (pin "2") (pinfunction "2_2") (pintype "bidirectional"))
      (node (ref "C7") (pin "-") (pinfunction "-_-") (pintype "passive"))
      (node (ref "C8") (pin "-") (pinfunction "-_-") (pintype "passive"))
      (node (ref "D1") (pin "2") (pinfunction "2_2") (pintype "bidirectional"))
      (node (ref "D2") (pin "2") (pinfunction "2_2") (pintype "bidirectional"))
      (node (ref "H12") (pin "1") (pinfunction "1_1") (pintype "bidirectional"))
      (node (ref "H12") (pin "2") (pinfunction "2_2") (pintype "bidirectional"))
      (node (ref "H12") (pin "3") (pinfunction "3_3") (pintype "bidirectional"))
      (node (ref "H12") (pin "4") (pinfunction "4_4") (pintype "bidirectional"))
      (node (ref "H15") (pin "1") (pinfunction "1_1") (pintype "bidirectional"))
      (node (ref "H15") (pin "2") (pinfunction "2_2") (pintype "bidirectional"))
      (node (ref "H15") (pin "3") (pinfunction "3_3") (pintype "bidirectional"))
      (node (ref "H15") (pin "4") (pinfunction "4_4") (pintype "bidirectional"))
      (node (ref "H18") (pin "1") (pinfunction "1_1") (pintype "bidirectional"))
      (node (ref "H18") (pin "2") (pinfunction "2_2") (pintype "bidirectional"))
      (node (ref "H18") (pin "3") (pinfunction "3_3") (pintype "bidirectional"))
      (node (ref "H18") (pin "4") (pinfunction "4_4") (pintype "bidirectional"))
      (node (ref "H21") (pin "2") (pinfunction "2_2") (pintype "bidirectional"))
      (node (ref "H22") (pin "2") (pinfunction "2_2") (pintype "bidirectional"))
      (node (ref "H23") (pin "2") (pinfunction "2_2") (pintype "bidirectional"))
      (node (ref "H24") (pin "4") (pinfunction "4_4") (pintype "bidirectional"))
      (node (ref "H25") (pin "2") (pinfunction "2_2") (pintype "bidirectional"))
      (node (ref "H27") (pin "3") (pinfunction "3_3") (pintype "bidirectional"))
      (node (ref "H3") (pin "1") (pinfunction "1_1") (pintype "bidirectional"))
      (node (ref "H3") (pin "2") (pinfunction "2_2") (pintype "bidirectional"))
      (node (ref "H3") (pin "3") (pinfunction "3_3") (pintype "bidirectional"))
      (node (ref "H3") (pin "4") (pinfunction "4_4") (pintype "bidirectional"))
      (node (ref "H6") (pin "1") (pinfunction "1_1") (pintype "bidirectional"))
      (node (ref "H6") (pin "2") (pinfunction "2_2") (pintype "bidirectional"))
      (node (ref "H6") (pin "3") (pinfunction "3_3") (pintype "bidirectional"))
      (node (ref "H6") (pin "4") (pinfunction "4_4") (pintype "bidirectional"))
      (node (ref "H9") (pin "1") (pinfunction "1_1") (pintype "bidirectional"))
      (node (ref "H9") (pin "2") (pinfunction "2_2") (pintype "bidirectional"))
      (node (ref "H9") (pin "3") (pinfunction "3_3") (pintype "bidirectional"))
      (node (ref "H9") (pin "4") (pinfunction "4_4") (pintype "bidirectional"))
      (node (ref "LED2") (pin "P$2") (pinfunction "2_P$2") (pintype "bidirectional"))
      (node (ref "Q1") (pin "1") (pinfunction "S_1") (pintype "bidirectional"))
      (node (ref "Q1") (pin "4") (pinfunction "S_4") (pintype "bidirectional"))
      (node (ref "R2") (pin "2") (pinfunction "2_2") (pintype "bidirectional"))
      (node (ref "R4") (pin "1") (pinfunction "1_1") (pintype "bidirectional"))
      (node (ref "R5") (pin "2") (pinfunction "2_2") (pintype "bidirectional"))
      (node (ref "U1") (pin "1") (pinfunction "A1_1") (pintype "bidirectional"))
      (node (ref "U1") (pin "2") (pinfunction "A0_2") (pintype "bidirectional"))
      (node (ref "U1") (pin "7") (pinfunction "GND_7") (pintype "bidirectional"))
      (node (ref "U10") (pin "10") (pinfunction "GND_10") (pintype "power_in"))
      (node (ref "U11") (pin "GND") (pinfunction "VSS_GND") (pintype "bidirectional"))
      (node (ref "U11") (pin "GND@1") (pinfunction "VSS_GND@1") (pintype "bidirectional"))
      (node (ref "U11") (pin "GND@2") (pinfunction "VSS_GND@2") (pintype "bidirectional"))
      (node (ref "U11") (pin "SHIELD") (pinfunction "SHIELD_SHIELD") (pintype "bidirectional"))
      (node (ref "U11") (pin "SHIELD@1") (pinfunction "SHIELD_SHIELD@1") (pintype "bidirectional"))
      (node (ref "U11") (pin "SHIELD@2") (pinfunction "SHIELD_SHIELD@2") (pintype "bidirectional"))
      (node (ref "U11") (pin "SHIELD@3") (pinfunction "SHIELD_SHIELD@3") (pintype "bidirectional"))
      (node (ref "U11") (pin "VSS") (pinfunction "VSS_VSS") (pintype "bidirectional"))
      (node (ref "U2") (pin "1") (pinfunction "PGND_1") (pintype "bidirectional"))
      (node (ref "U2") (pin "5") (pinfunction "FB_5") (pintype "bidirectional"))
      (node (ref "U2") (pin "6") (pinfunction "AGND_6") (pintype "bidirectional"))
      (node (ref "U2") (pin "PAD") (pinfunction "PGND_PAD") (pintype "bidirectional"))
      (node (ref "U3") (pin "6") (pinfunction "GND_6") (pintype "bidirectional"))
      (node (ref "U3") (pin "PAD") (pinfunction "GND_PAD") (pintype "bidirectional"))
      (node (ref "U4") (pin "12") (pinfunction "GND_12") (pintype "bidirectional"))
      (node (ref "U4") (pin "2") (pinfunction "GND_2") (pintype "bidirectional"))
      (node (ref "U4") (pin "7") (pinfunction "SENSE_7") (pintype "bidirectional"))
      (node (ref "U4") (pin "PAD") (pinfunction "GND_PAD") (pintype "bidirectional"))
      (node (ref "U5") (pin "12") (pinfunction "GND_12") (pintype "bidirectional"))
      (node (ref "U5") (pin "2") (pinfunction "GND_2") (pintype "bidirectional"))
      (node (ref "U5") (pin "7") (pinfunction "SENSE_7") (pintype "bidirectional"))
      (node (ref "U5") (pin "PAD") (pinfunction "GND_PAD") (pintype "bidirectional"))
      (node (ref "U6") (pin "12") (pinfunction "GND_12") (pintype "bidirectional"))
      (node (ref "U6") (pin "2") (pinfunction "GND_2") (pintype "bidirectional"))
      (node (ref "U6") (pin "7") (pinfunction "SENSE_7") (pintype "bidirectional"))
      (node (ref "U6") (pin "PAD") (pinfunction "GND_PAD") (pintype "bidirectional"))
      (node (ref "U7") (pin "12") (pinfunction "GND_12") (pintype "bidirectional"))
      (node (ref "U7") (pin "2") (pinfunction "GND_2") (pintype "bidirectional"))
      (node (ref "U7") (pin "7") (pinfunction "SENSE_7") (pintype "bidirectional"))
      (node (ref "U7") (pin "PAD") (pinfunction "GND_PAD") (pintype "bidirectional"))
      (node (ref "U8") (pin "15") (pinfunction "A0_15") (pintype "bidirectional"))
      (node (ref "U8") (pin "16") (pinfunction "A1_16") (pintype "bidirectional"))
      (node (ref "U8") (pin "6") (pinfunction "GND_6") (pintype "bidirectional"))
      (node (ref "U8") (pin "PAD") (pinfunction "GND_PAD") (pintype "bidirectional"))
      (node (ref "U9") (pin "1") (pinfunction "CLKIN_1") (pintype "bidirectional"))
      (node (ref "U9") (pin "11") (pinfunction "FSYNC_11") (pintype "bidirectional"))
      (node (ref "U9") (pin "18") (pinfunction "GND_18") (pintype "bidirectional"))
      (node (ref "U9") (pin "9") (pinfunction "AD0_9") (pintype "bidirectional"))
    )
    (net (code "65") (name "Net-(H23-Pad1)") (class "Default")
      (node (ref "H23") (pin "1") (pinfunction "1_1") (pintype "bidirectional"))
      (node (ref "J5") (pin "3") (pinfunction "3_3") (pintype "bidirectional"))
    )
    (net (code "66") (name "Net-(LED0-2)") (class "Default")
      (node (ref "LED0") (pin "P$2") (pinfunction "2_P$2") (pintype "bidirectional"))
      (node (ref "R2") (pin "1") (pinfunction "1_1") (pintype "bidirectional"))
    )
    (net (code "67") (name "Net-(LED1-2)") (class "Default")
      (node (ref "LED1") (pin "P$2") (pinfunction "2_P$2") (pintype "bidirectional"))
      (node (ref "R5") (pin "1") (pinfunction "1_1") (pintype "bidirectional"))
    )
    (net (code "68") (name "Net-(LED2-1)") (class "Default")
      (node (ref "LED2") (pin "P$1") (pinfunction "1_P$1") (pintype "bidirectional"))
      (node (ref "R9") (pin "2") (pinfunction "2_2") (pintype "bidirectional"))
    )
    (net (code "69") (name "Net-(U1-VIN+)") (class "Default")
      (node (ref "C1") (pin "+") (pinfunction "+_+") (pintype "passive"))
      (node (ref "D1") (pin "1") (pinfunction "1_1") (pintype "bidirectional"))
      (node (ref "H27") (pin "2") (pinfunction "2_2") (pintype "bidirectional"))
      (node (ref "R1") (pin "1") (pinfunction "1_1") (pintype "bidirectional"))
      (node (ref "U1") (pin "10") (pinfunction "VIN+_10") (pintype "bidirectional"))
    )
    (net (code "70") (name "Net-(U2-SW)") (class "Default")
      (node (ref "L1") (pin "1") (pinfunction "1_1") (pintype "passive"))
      (node (ref "U2") (pin "9") (pinfunction "SW_9") (pintype "bidirectional"))
    )
    (net (code "71") (name "Net-(U3-BOOT)") (class "Default")
      (node (ref "C6") (pin "1") (pinfunction "1_1") (pintype "bidirectional"))
      (node (ref "U3") (pin "1") (pinfunction "BOOT_1") (pintype "bidirectional"))
    )
    (net (code "72") (name "Net-(U3-PH)") (class "Default")
      (node (ref "C6") (pin "2") (pinfunction "2_2") (pintype "bidirectional"))
      (node (ref "D2") (pin "1") (pinfunction "1_1") (pintype "bidirectional"))
      (node (ref "L2") (pin "1") (pinfunction "1_1") (pintype "passive"))
      (node (ref "U3") (pin "8") (pinfunction "PH_8") (pintype "bidirectional"))
    )
    (net (code "73") (name "Net-(U3-VSENSE)") (class "Default")
      (node (ref "R3") (pin "1") (pinfunction "1_1") (pintype "bidirectional"))
      (node (ref "R4") (pin "2") (pinfunction "2_2") (pintype "bidirectional"))
      (node (ref "U3") (pin "4") (pinfunction "VSENSE_4") (pintype "bidirectional"))
    )
    (net (code "74") (name "Net-(U4-CP1)") (class "Default")
      (node (ref "C9") (pin "2") (pinfunction "2_2") (pintype "bidirectional"))
      (node (ref "U4") (pin "10") (pinfunction "CP1_10") (pintype "bidirectional"))
    )
    (net (code "75") (name "Net-(U4-CP2)") (class "Default")
      (node (ref "C9") (pin "1") (pinfunction "1_1") (pintype "bidirectional"))
      (node (ref "U4") (pin "11") (pinfunction "CP2_11") (pintype "bidirectional"))
    )
    (net (code "76") (name "Net-(U4-VCP)") (class "Default")
      (node (ref "C10") (pin "2") (pinfunction "2_2") (pintype "bidirectional"))
      (node (ref "U4") (pin "13") (pinfunction "VCP_13") (pintype "bidirectional"))
    )
    (net (code "77") (name "Net-(U5-CP1)") (class "Default")
      (node (ref "C12") (pin "2") (pinfunction "2_2") (pintype "bidirectional"))
      (node (ref "U5") (pin "10") (pinfunction "CP1_10") (pintype "bidirectional"))
    )
    (net (code "78") (name "Net-(U5-CP2)") (class "Default")
      (node (ref "C12") (pin "1") (pinfunction "1_1") (pintype "bidirectional"))
      (node (ref "U5") (pin "11") (pinfunction "CP2_11") (pintype "bidirectional"))
    )
    (net (code "79") (name "Net-(U5-VCP)") (class "Default")
      (node (ref "C13") (pin "2") (pinfunction "2_2") (pintype "bidirectional"))
      (node (ref "U5") (pin "13") (pinfunction "VCP_13") (pintype "bidirectional"))
    )
    (net (code "80") (name "Net-(U6-CP1)") (class "Default")
      (node (ref "C16") (pin "2") (pinfunction "2_2") (pintype "bidirectional"))
      (node (ref "U6") (pin "10") (pinfunction "CP1_10") (pintype "bidirectional"))
    )
    (net (code "81") (name "Net-(U6-CP2)") (class "Default")
      (node (ref "C16") (pin "1") (pinfunction "1_1") (pintype "bidirectional"))
      (node (ref "U6") (pin "11") (pinfunction "CP2_11") (pintype "bidirectional"))
    )
    (net (code "82") (name "Net-(U6-VCP)") (class "Default")
      (node (ref "C17") (pin "2") (pinfunction "2_2") (pintype "bidirectional"))
      (node (ref "U6") (pin "13") (pinfunction "VCP_13") (pintype "bidirectional"))
    )
    (net (code "83") (name "Net-(U7-CP1)") (class "Default")
      (node (ref "C19") (pin "2") (pinfunction "2_2") (pintype "bidirectional"))
      (node (ref "U7") (pin "10") (pinfunction "CP1_10") (pintype "bidirectional"))
    )
    (net (code "84") (name "Net-(U7-CP2)") (class "Default")
      (node (ref "C19") (pin "1") (pinfunction "1_1") (pintype "bidirectional"))
      (node (ref "U7") (pin "11") (pinfunction "CP2_11") (pintype "bidirectional"))
    )
    (net (code "85") (name "Net-(U7-VCP)") (class "Default")
      (node (ref "C20") (pin "2") (pinfunction "2_2") (pintype "bidirectional"))
      (node (ref "U7") (pin "13") (pinfunction "VCP_13") (pintype "bidirectional"))
    )
    (net (code "86") (name "Net-(U8-~{INT})") (class "Default")
      (node (ref "J21") (pin "2") (pinfunction "2_2") (pintype "bidirectional"))
      (node (ref "U8") (pin "11") (pinfunction "~{INT}_11") (pintype "bidirectional"))
    )
    (net (code "87") (name "Net-(U9-CPOUT)") (class "Default")
      (node (ref "C23") (pin "1") (pinfunction "1_1") (pintype "bidirectional"))
      (node (ref "U9") (pin "20") (pinfunction "CPOUT_20") (pintype "bidirectional"))
    )
    (net (code "88") (name "Net-(U9-REGOUT)") (class "Default")
      (node (ref "C24") (pin "2") (pinfunction "2_2") (pintype "bidirectional"))
      (node (ref "U9") (pin "10") (pinfunction "REGOUT_10") (pintype "bidirectional"))
    )
    (net (code "89") (name "VBAT") (class "Default")
      (node (ref "C2") (pin "1") (pinfunction "1_1") (pintype "bidirectional"))
      (node (ref "C5") (pin "1") (pinfunction "1_1") (pintype "bidirectional"))
      (node (ref "H27") (pin "1") (pinfunction "1_1") (pintype "bidirectional"))
      (node (ref "J1") (pin "1") (pinfunction "1_1") (pintype "bidirectional"))
      (node (ref "J11") (pin "1") (pinfunction "1_1") (pintype "bidirectional"))
      (node (ref "J14") (pin "1") (pinfunction "1_1") (pintype "bidirectional"))
      (node (ref "J17") (pin "1") (pinfunction "1_1") (pintype "bidirectional"))
      (node (ref "J20") (pin "1") (pinfunction "1_1") (pintype "bidirectional"))
      (node (ref "J4") (pin "1") (pinfunction "1_1") (pintype "bidirectional"))
      (node (ref "J5") (pin "1") (pinfunction "1_1") (pintype "bidirectional"))
      (node (ref "J8") (pin "1") (pinfunction "1_1") (pintype "bidirectional"))
      (node (ref "R1") (pin "2") (pinfunction "2_2") (pintype "bidirectional"))
      (node (ref "U1") (pin "8") (pinfunction "VBUS_8") (pintype "bidirectional"))
      (node (ref "U1") (pin "9") (pinfunction "VIN-_9") (pintype "bidirectional"))
      (node (ref "U2") (pin "2") (pinfunction "VIN_2") (pintype "bidirectional"))
      (node (ref "U2") (pin "3") (pinfunction "EN_3") (pintype "bidirectional"))
      (node (ref "U3") (pin "7") (pinfunction "VIN_7") (pintype "bidirectional"))
    )
    (net (code "90") (name "VFET") (class "Default")
      (node (ref "D3") (pin "1") (pinfunction "1_1") (pintype "bidirectional"))
      (node (ref "D4") (pin "1") (pinfunction "1_1") (pintype "bidirectional"))
      (node (ref "H19") (pin "1") (pinfunction "1_1") (pintype "bidirectional"))
      (node (ref "H19") (pin "2") (pinfunction "2_2") (pintype "bidirectional"))
      (node (ref "J5") (pin "2") (pinfunction "2_2") (pintype "bidirectional"))
    )
    (net (code "91") (name "VMOTOR") (class "Default")
      (node (ref "C11") (pin "1") (pinfunction "1_1") (pintype "bidirectional"))
      (node (ref "C14") (pin "1") (pinfunction "1_1") (pintype "bidirectional"))
      (node (ref "C15") (pin "+") (pinfunction "+_+") (pintype "passive"))
      (node (ref "C18") (pin "1") (pinfunction "1_1") (pintype "bidirectional"))
      (node (ref "C21") (pin "1") (pinfunction "1_1") (pintype "bidirectional"))
      (node (ref "C8") (pin "+") (pinfunction "+_+") (pintype "passive"))
      (node (ref "J20") (pin "2") (pinfunction "2_2") (pintype "bidirectional"))
      (node (ref "U4") (pin "8") (pinfunction "VMOT_8") (pintype "bidirectional"))
      (node (ref "U5") (pin "8") (pinfunction "VMOT_8") (pintype "bidirectional"))
      (node (ref "U6") (pin "8") (pinfunction "VMOT_8") (pintype "bidirectional"))
      (node (ref "U7") (pin "8") (pinfunction "VMOT_8") (pintype "bidirectional"))
    )
    (net (code "92") (name "unconnected-(U2-PG-Pad7)") (class "Default")
      (node (ref "U2") (pin "7") (pinfunction "PG_7") (pintype "bidirectional"))
    )
    (net (code "93") (name "unconnected-(U3-ENA-Pad5)") (class "Default")
      (node (ref "U3") (pin "5") (pinfunction "ENA_5") (pintype "bidirectional"))
    )
    (net (code "94") (name "unconnected-(U4-VREG-Pad14)") (class "Default")
      (node (ref "U4") (pin "14") (pinfunction "VREG_14") (pintype "bidirectional"))
    )
    (net (code "95") (name "unconnected-(U4-~{FAULT}-Pad15)") (class "Default")
      (node (ref "U4") (pin "15") (pinfunction "~{FAULT}_15") (pintype "bidirectional"))
    )
    (net (code "96") (name "unconnected-(U5-VREG-Pad14)") (class "Default")
      (node (ref "U5") (pin "14") (pinfunction "VREG_14") (pintype "bidirectional"))
    )
    (net (code "97") (name "unconnected-(U5-~{FAULT}-Pad15)") (class "Default")
      (node (ref "U5") (pin "15") (pinfunction "~{FAULT}_15") (pintype "bidirectional"))
    )
    (net (code "98") (name "unconnected-(U6-VREG-Pad14)") (class "Default")
      (node (ref "U6") (pin "14") (pinfunction "VREG_14") (pintype "bidirectional"))
    )
    (net (code "99") (name "unconnected-(U6-~{FAULT}-Pad15)") (class "Default")
      (node (ref "U6") (pin "15") (pinfunction "~{FAULT}_15") (pintype "bidirectional"))
    )
    (net (code "100") (name "unconnected-(U7-VREG-Pad14)") (class "Default")
      (node (ref "U7") (pin "14") (pinfunction "VREG_14") (pintype "bidirectional"))
    )
    (net (code "101") (name "unconnected-(U7-~{FAULT}-Pad15)") (class "Default")
      (node (ref "U7") (pin "15") (pinfunction "~{FAULT}_15") (pintype "bidirectional"))
    )
    (net (code "102") (name "unconnected-(U9-AUX_CL-Pad7)") (class "Default")
      (node (ref "U9") (pin "7") (pinfunction "AUX_CL_7") (pintype "bidirectional"))
    )
    (net (code "103") (name "unconnected-(U9-AUX_DA-Pad6)") (class "Default")
      (node (ref "U9") (pin "6") (pinfunction "AUX_DA_6") (pintype "bidirectional"))
    )
    (net (code "104") (name "unconnected-(U9-CLKOUT-Pad22)") (class "Default")
      (node (ref "U9") (pin "22") (pinfunction "CLKOUT_22") (pintype "bidirectional"))
    )
    (net (code "105") (name "unconnected-(U10-CTS-Pad12)") (class "Default")
      (node (ref "U10") (pin "12") (pinfunction "CTS_12") (pintype "output"))
    )
    (net (code "106") (name "unconnected-(U10-DIO0-Pad20)") (class "Default")
      (node (ref "U10") (pin "20") (pinfunction "DIO0_20") (pintype "bidirectional"))
    )
    (net (code "107") (name "unconnected-(U10-DIO1-Pad19)") (class "Default")
      (node (ref "U10") (pin "19") (pinfunction "DIO1_19") (pintype "bidirectional"))
    )
    (net (code "108") (name "unconnected-(U10-DIO2-Pad18)") (class "Default")
      (node (ref "U10") (pin "18") (pinfunction "DIO2_18") (pintype "bidirectional"))
    )
    (net (code "109") (name "unconnected-(U10-DIO3-Pad17)") (class "Default")
      (node (ref "U10") (pin "17") (pinfunction "DIO3_17") (pintype "bidirectional"))
    )
    (net (code "110") (name "unconnected-(U10-DIO4-Pad11)") (class "Default")
      (node (ref "U10") (pin "11") (pinfunction "DIO4_11") (pintype "bidirectional"))
    )
    (net (code "111") (name "unconnected-(U10-DIO5-Pad15)") (class "Default")
      (node (ref "U10") (pin "15") (pinfunction "DIO5_15") (pintype "bidirectional"))
    )
    (net (code "112") (name "unconnected-(U10-DIO11-Pad7)") (class "Default")
      (node (ref "U10") (pin "7") (pinfunction "DIO11_7") (pintype "bidirectional"))
    )
    (net (code "113") (name "unconnected-(U10-DIO12-Pad4)") (class "Default")
      (node (ref "U10") (pin "4") (pinfunction "DIO12_4") (pintype "bidirectional"))
    )
    (net (code "114") (name "unconnected-(U10-DTR-Pad9)") (class "Default")
      (node (ref "U10") (pin "9") (pinfunction "DTR_9") (pintype "bidirectional"))
    )
    (net (code "115") (name "unconnected-(U10-RES-Pad8)") (class "Default")
      (node (ref "U10") (pin "8") (pinfunction "RES_8") (pintype "bidirectional"))
    )
    (net (code "116") (name "unconnected-(U10-RES-Pad14)") (class "Default")
      (node (ref "U10") (pin "14") (pinfunction "RES_14") (pintype "bidirectional"))
    )
    (net (code "117") (name "unconnected-(U10-RESET-Pad5)") (class "Default")
      (node (ref "U10") (pin "5") (pinfunction "RESET_5") (pintype "input"))
    )
    (net (code "118") (name "unconnected-(U10-RSSI-Pad6)") (class "Default")
      (node (ref "U10") (pin "6") (pinfunction "RSSI_6") (pintype "bidirectional"))
    )
    (net (code "119") (name "unconnected-(U10-RTS-Pad16)") (class "Default")
      (node (ref "U10") (pin "16") (pinfunction "RTS_16") (pintype "input"))
    )
    (net (code "120") (name "unconnected-(U11-DETECT-PadCD)") (class "Default")
      (node (ref "U11") (pin "CD") (pinfunction "DETECT_CD") (pintype "bidirectional"))
    )
  )
)
